# Auto2018.net
KiCad netlist of a schematic drawn in EAGLE
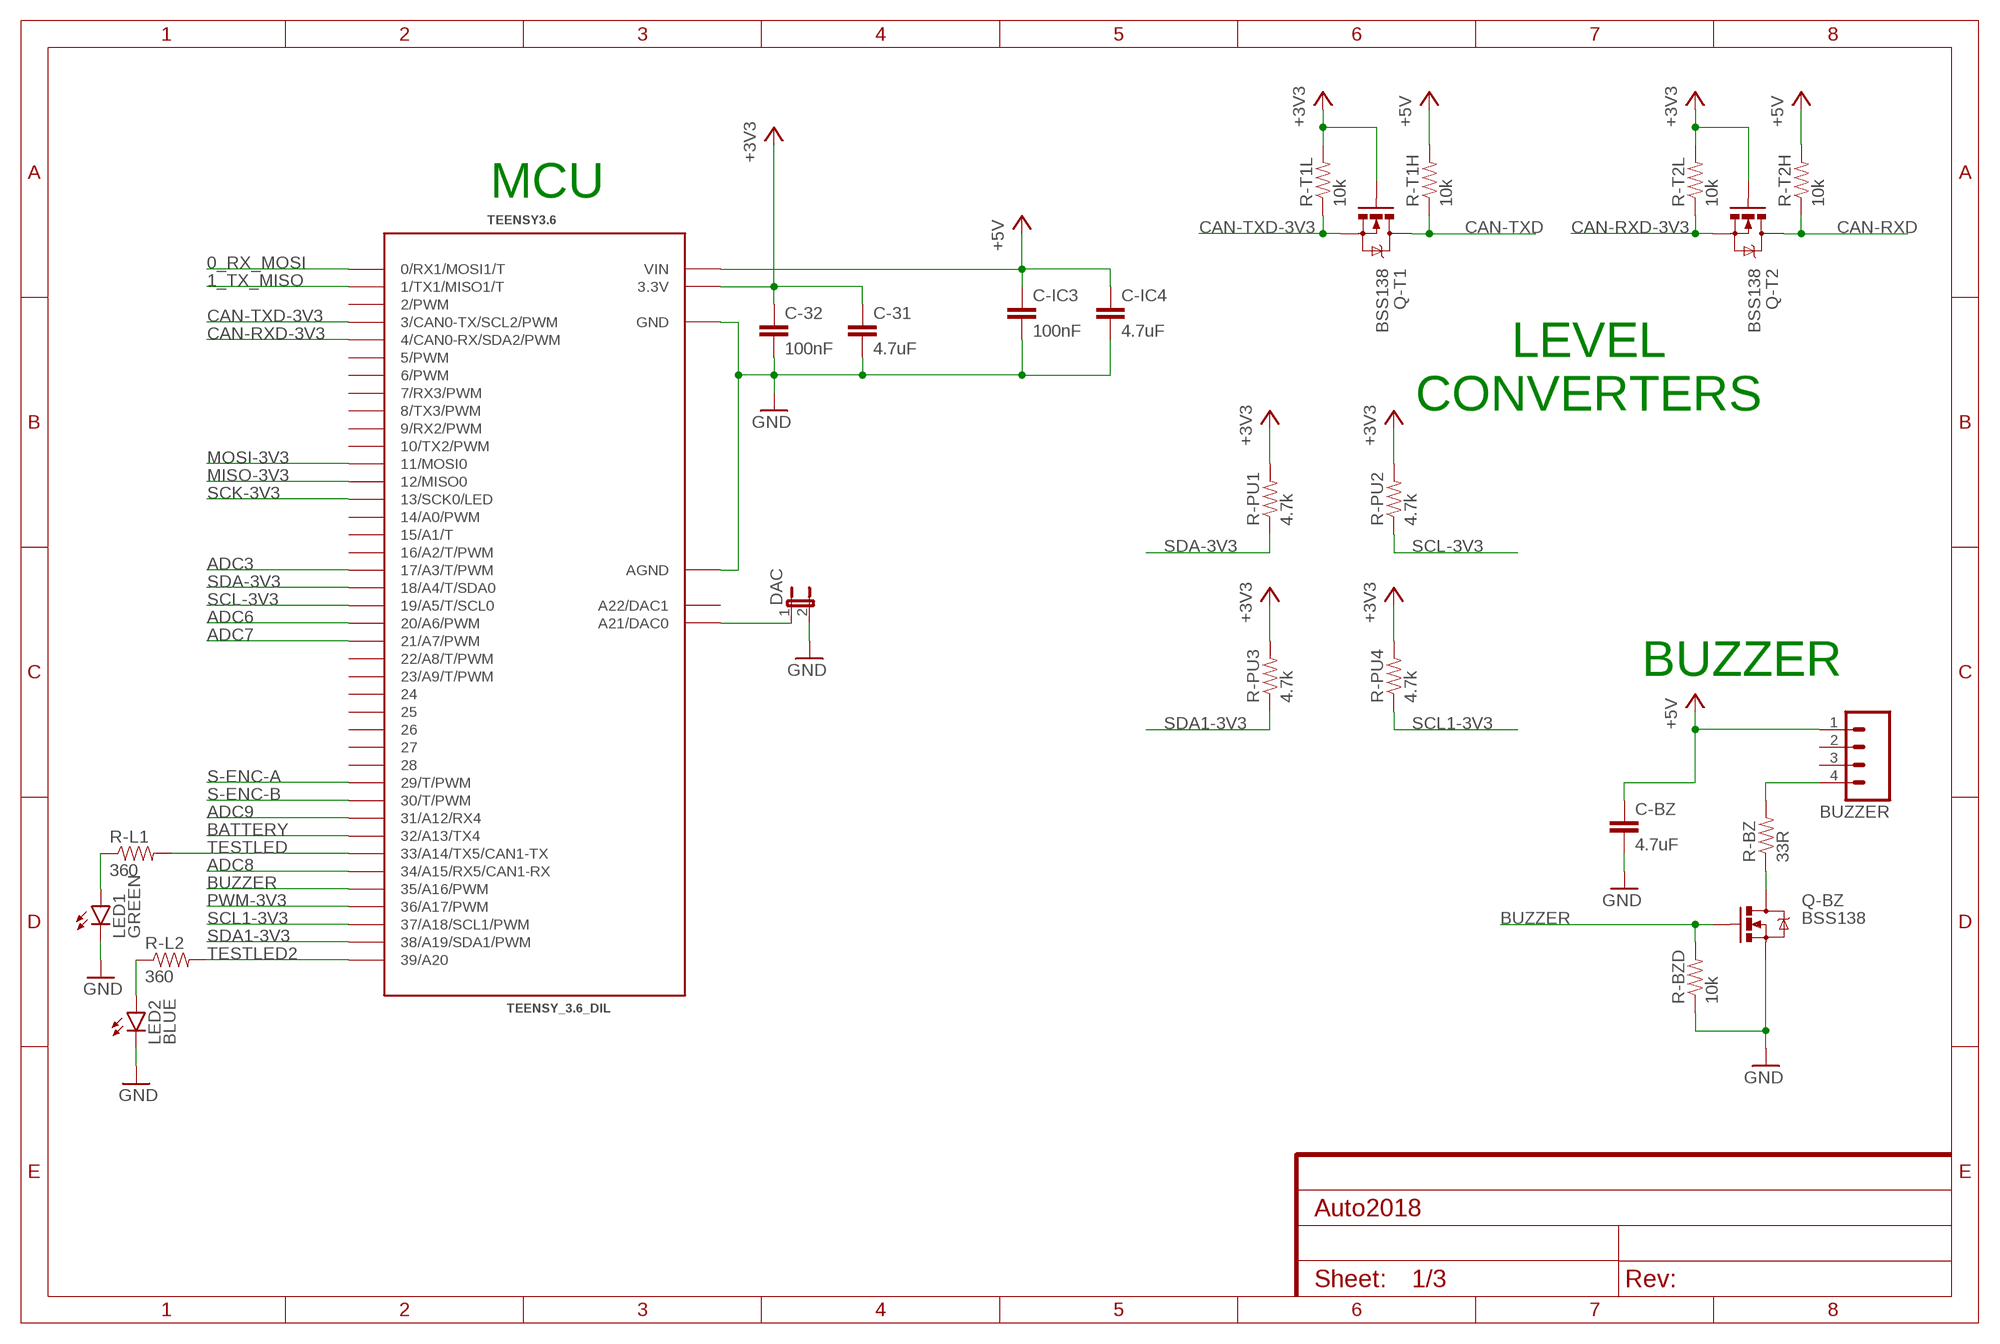
[diagram p0: schematic, sheet 1]
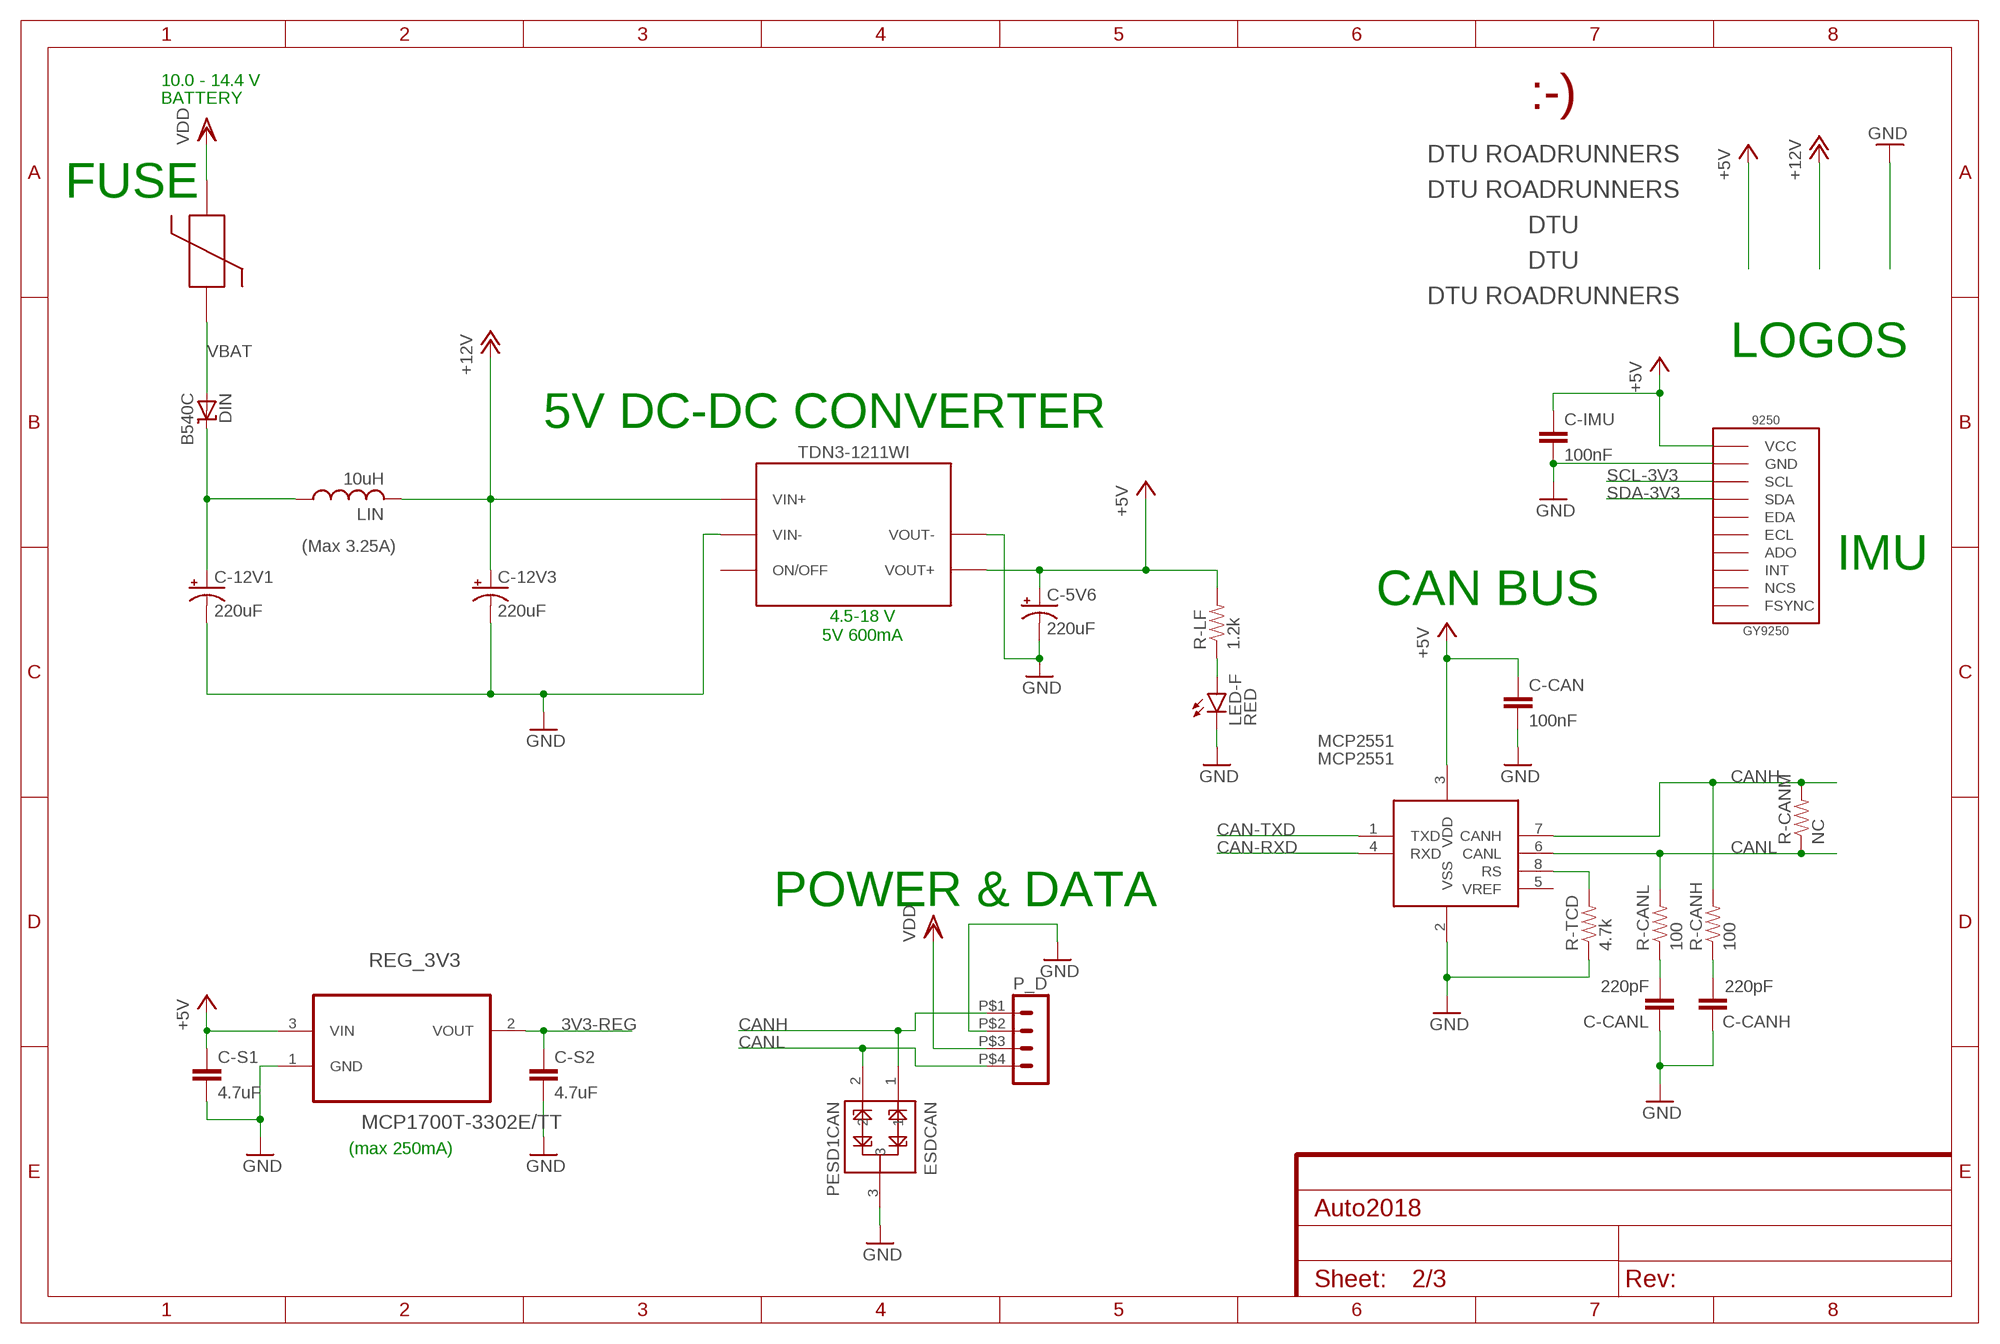
[diagram p1: schematic, sheet 2]
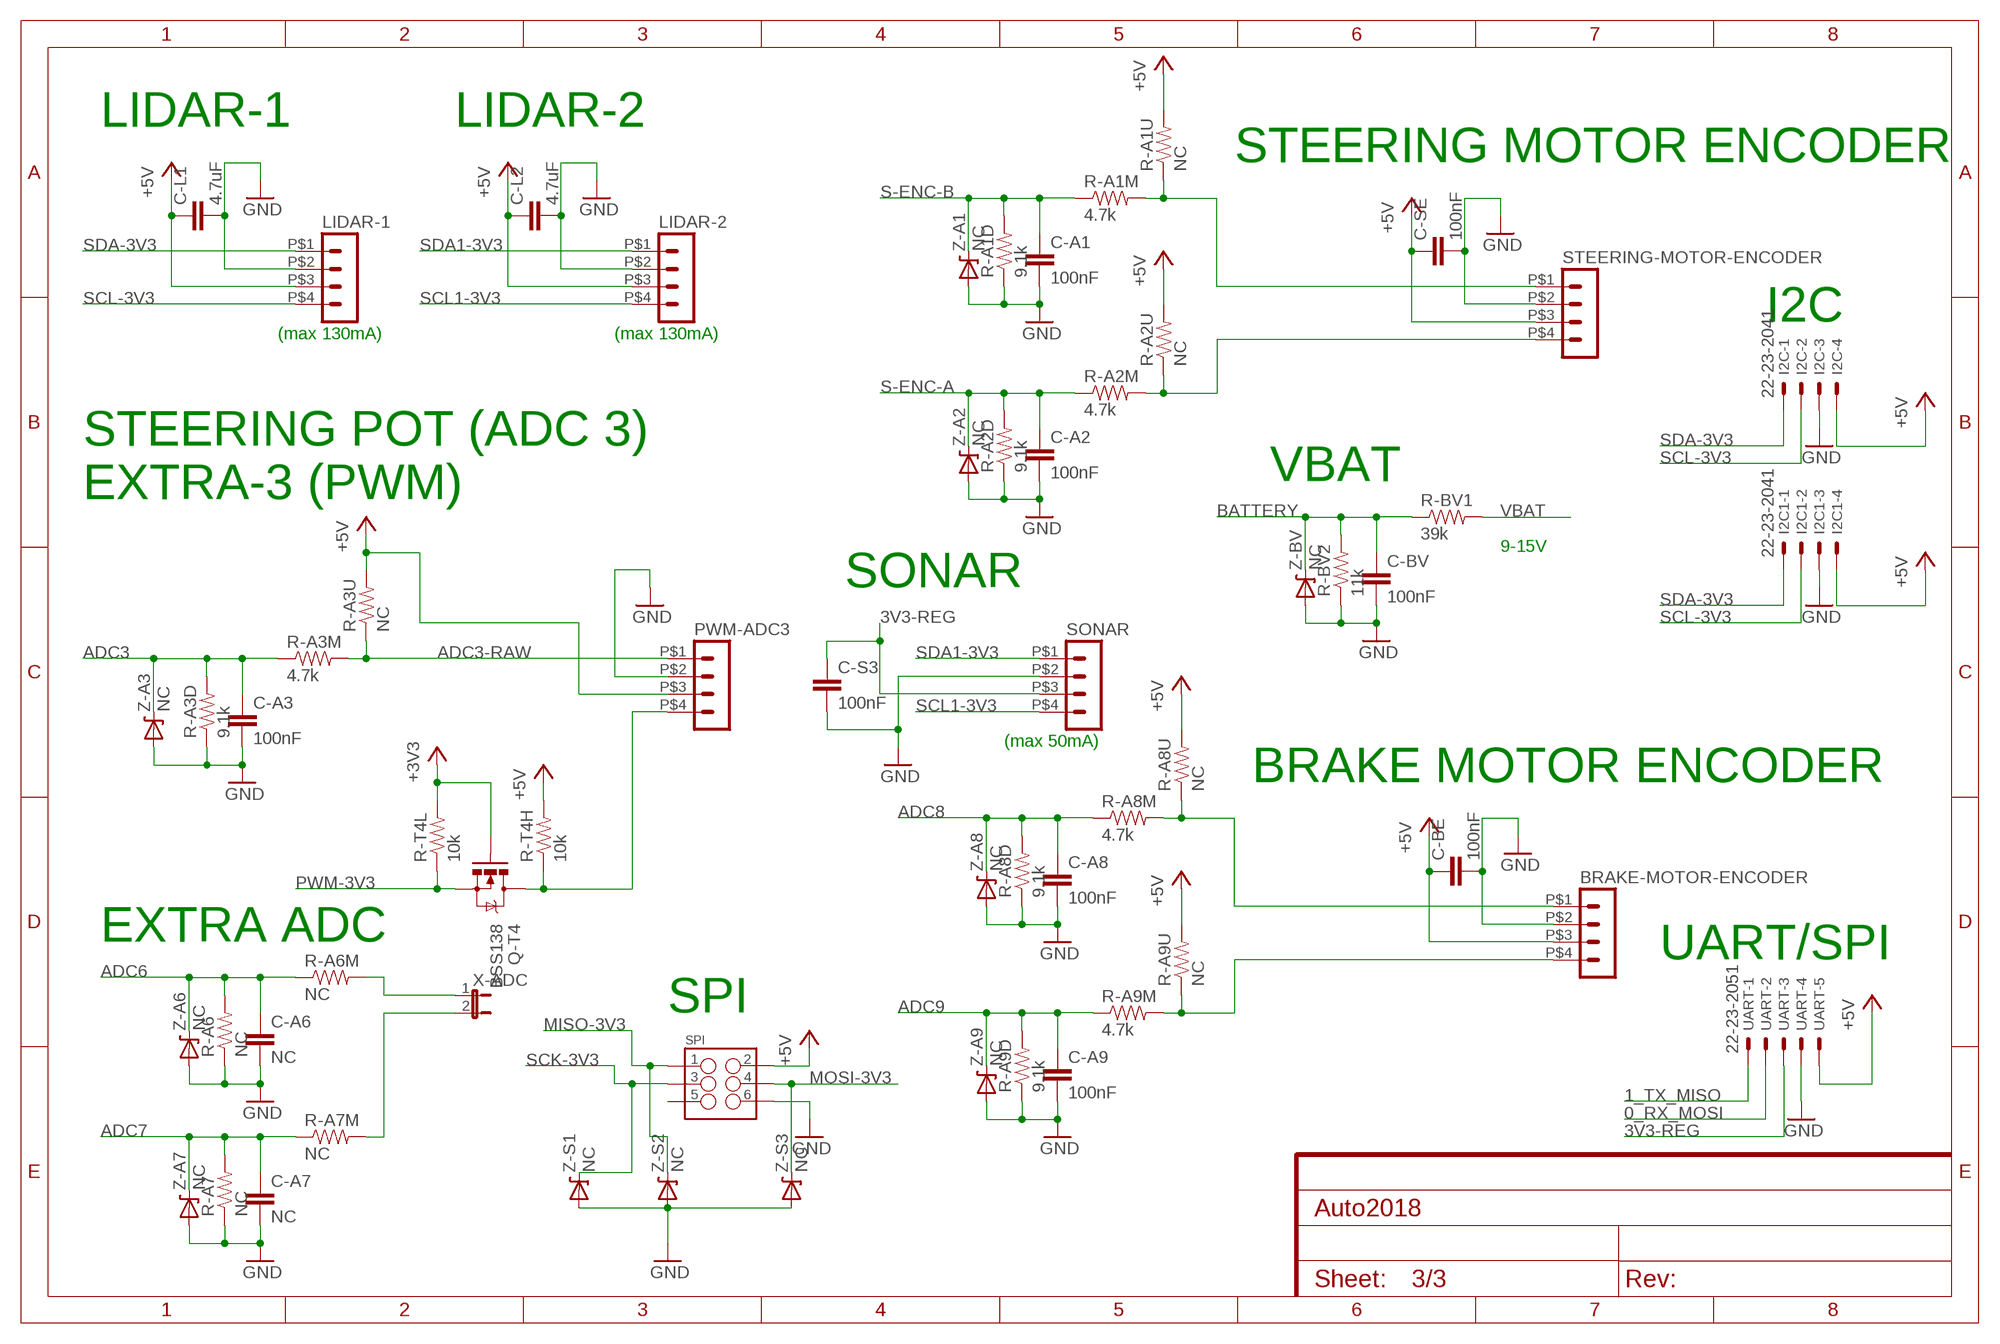
[diagram p2: schematic, sheet 3]

(export (version "E")
  (design (tool "Eeschema 10.0.6"))
  (components
    (comp (ref "BUZZER")
      (value "M04POLAR")
      (footprint "eagle-import:MOLEX-1X4")
      (libsource (lib "eagle-import") (part "M04POLAR"))
    )
    (comp (ref "C-31")
      (value "4.7uF")
      (footprint "eagle-import:1210")
      (libsource (lib "eagle-import") (part "CAP1210"))
    )
    (comp (ref "C-32")
      (value "100nF")
      (footprint "eagle-import:0805")
      (libsource (lib "eagle-import") (part "CAP0805"))
    )
    (comp (ref "C-BZ")
      (value "4.7uF")
      (footprint "eagle-import:1210")
      (libsource (lib "eagle-import") (part "CAP1210"))
    )
    (comp (ref "C-IC3")
      (value "100nF")
      (footprint "eagle-import:0805")
      (libsource (lib "eagle-import") (part "CAP0805"))
    )
    (comp (ref "C-IC4")
      (value "4.7uF")
      (footprint "eagle-import:1210")
      (libsource (lib "eagle-import") (part "CAP1210"))
    )
    (comp (ref "DAC")
      (value "JUMPER-2PTH")
      (footprint "eagle-import:1X02")
      (libsource (lib "eagle-import") (part "JUMPER-2PTH"))
    )
    (comp (ref "LED1")
      (value "GREEN")
      (footprint "eagle-import:LED-1206")
      (libsource (lib "eagle-import") (part "LED1206"))
    )
    (comp (ref "LED2")
      (value "BLUE")
      (footprint "eagle-import:LED-1206")
      (libsource (lib "eagle-import") (part "LED1206"))
    )
    (comp (ref "Q-BZ")
      (value "BSS138")
      (footprint "eagle-import:SOT23-3")
      (libsource (lib "eagle-import") (part "MOSFET-NCHANNELBSS123LT1G"))
    )
    (comp (ref "Q-T1")
      (value "BSS138")
      (footprint "eagle-import:SOT23-3")
      (libsource (lib "eagle-import") (part "MOSFET-NCHANNELBSS123LT1G"))
    )
    (comp (ref "Q-T2")
      (value "BSS138")
      (footprint "eagle-import:SOT23-3")
      (libsource (lib "eagle-import") (part "MOSFET-NCHANNELBSS123LT1G"))
    )
    (comp (ref "R-BZ")
      (value "33R")
      (footprint "eagle-import:0805")
      (libsource (lib "eagle-import") (part "RESISTOR0805-RES"))
    )
    (comp (ref "R-BZD")
      (value "10k")
      (footprint "eagle-import:0805")
      (libsource (lib "eagle-import") (part "RESISTOR0805-RES"))
    )
    (comp (ref "R-L1")
      (value "360")
      (footprint "eagle-import:0805")
      (libsource (lib "eagle-import") (part "RESISTOR0805-RES"))
    )
    (comp (ref "R-L2")
      (value "360")
      (footprint "eagle-import:0805")
      (libsource (lib "eagle-import") (part "RESISTOR0805-RES"))
    )
    (comp (ref "R-PU1")
      (value "4.7k")
      (footprint "eagle-import:0805")
      (libsource (lib "eagle-import") (part "RESISTOR0805-RES"))
    )
    (comp (ref "R-PU2")
      (value "4.7k")
      (footprint "eagle-import:0805")
      (libsource (lib "eagle-import") (part "RESISTOR0805-RES"))
    )
    (comp (ref "R-PU3")
      (value "4.7k")
      (footprint "eagle-import:0805")
      (libsource (lib "eagle-import") (part "RESISTOR0805-RES"))
    )
    (comp (ref "R-PU4")
      (value "4.7k")
      (footprint "eagle-import:0805")
      (libsource (lib "eagle-import") (part "RESISTOR0805-RES"))
    )
    (comp (ref "R-T1H")
      (value "10k")
      (footprint "eagle-import:0805")
      (libsource (lib "eagle-import") (part "RESISTOR0805-RES"))
    )
    (comp (ref "R-T1L")
      (value "10k")
      (footprint "eagle-import:0805")
      (libsource (lib "eagle-import") (part "RESISTOR0805-RES"))
    )
    (comp (ref "R-T2H")
      (value "10k")
      (footprint "eagle-import:0805")
      (libsource (lib "eagle-import") (part "RESISTOR0805-RES"))
    )
    (comp (ref "R-T2L")
      (value "10k")
      (footprint "eagle-import:0805")
      (libsource (lib "eagle-import") (part "RESISTOR0805-RES"))
    )
    (comp (ref "TEENSY3.6")
      (value "TEENSY_3.6_DIL")
      (footprint "eagle-import:TEENSY_3.6_DIL")
      (libsource (lib "eagle-import") (part "TEENSY_3.6_DIL"))
    )
    (comp (ref "9250")
      (value "GY9250")
      (footprint "eagle-import:GY9250")
      (libsource (lib "eagle-import") (part "GY9250"))
    )
    (comp (ref "C-5V6")
      (value "220uF")
      (footprint "eagle-import:PANASONIC_D")
      (libsource (lib "eagle-import") (part "CPOL-USD"))
    )
    (comp (ref "C-12V1")
      (value "220uF")
      (footprint "eagle-import:PANASONIC_D")
      (libsource (lib "eagle-import") (part "CPOL-USD"))
    )
    (comp (ref "C-12V3")
      (value "220uF")
      (footprint "eagle-import:PANASONIC_D")
      (libsource (lib "eagle-import") (part "CPOL-USD"))
    )
    (comp (ref "C-CAN")
      (value "100nF")
      (footprint "eagle-import:0805")
      (libsource (lib "eagle-import") (part "CAP0805"))
    )
    (comp (ref "C-CANH")
      (value "220pF")
      (footprint "eagle-import:0805")
      (libsource (lib "eagle-import") (part "CAP0805"))
    )
    (comp (ref "C-CANL")
      (value "220pF")
      (footprint "eagle-import:0805")
      (libsource (lib "eagle-import") (part "CAP0805"))
    )
    (comp (ref "C-IMU")
      (value "100nF")
      (footprint "eagle-import:0805")
      (libsource (lib "eagle-import") (part "CAP0805"))
    )
    (comp (ref "C-S1")
      (value "4.7uF")
      (footprint "eagle-import:1210")
      (libsource (lib "eagle-import") (part "CAP1210"))
    )
    (comp (ref "C-S2")
      (value "4.7uF")
      (footprint "eagle-import:1210")
      (libsource (lib "eagle-import") (part "CAP1210"))
    )
    (comp (ref "DIN")
      (value "B540C")
      (footprint "eagle-import:SMC")
      (libsource (lib "eagle-import") (part "SD-SMC"))
    )
    (comp (ref "ESDCAN")
      (value "PESD1CAN")
      (footprint "eagle-import:SOT23-3")
      (libsource (lib "eagle-import") (part "PESD1CAN"))
    )
    (comp (ref "LED-F")
      (value "RED")
      (footprint "eagle-import:LED-1206")
      (libsource (lib "eagle-import") (part "LED1206"))
    )
    (comp (ref "LIN")
      (value "10uH")
      (footprint "eagle-import:WE-LHMI_SMD_POWER_INDUCTOR")
      (libsource (lib "eagle-import") (part "WE-LHMI_SMD_POWER_INDUCTOR"))
    )
    (comp (ref "MAIN_FUSE")
      (value "SMF_OMNI-BLOK_FUSE_BLOCK")
      (footprint "eagle-import:SMF_OMNI-BLOK_FUSE_BLOCK")
      (libsource (lib "eagle-import") (part "SMF_OMNI-BLOK_FUSE_BLOCK"))
    )
    (comp (ref "MCP2551")
      (value "MCP2551")
      (footprint "eagle-import:SO-08M")
      (libsource (lib "eagle-import") (part "MCP2551"))
    )
    (comp (ref "P_D")
      (value "HEADER_POS4_43045-0401")
      (footprint "eagle-import:43045-0400")
      (libsource (lib "eagle-import") (part "HEADER_POS4_?43045-0401"))
    )
    (comp (ref "R-CANH")
      (value "100")
      (footprint "eagle-import:0805")
      (libsource (lib "eagle-import") (part "RESISTOR0805-RES"))
    )
    (comp (ref "R-CANL")
      (value "100")
      (footprint "eagle-import:0805")
      (libsource (lib "eagle-import") (part "RESISTOR0805-RES"))
    )
    (comp (ref "R-CANM")
      (value "NC")
      (footprint "eagle-import:0805")
      (libsource (lib "eagle-import") (part "RESISTOR0805-RES"))
    )
    (comp (ref "R-LF")
      (value "1.2k")
      (footprint "eagle-import:0805")
      (libsource (lib "eagle-import") (part "RESISTOR0805-RES"))
    )
    (comp (ref "R-TCD")
      (value "4.7k")
      (footprint "eagle-import:0805")
      (libsource (lib "eagle-import") (part "RESISTOR0805-RES"))
    )
    (comp (ref "REG_3V3")
      (value "MCP1700T-3302E/TT")
      (footprint "eagle-import:SOT95P237X112-3N")
      (libsource (lib "eagle-import") (part "MCP1700T-3302E/TT"))
    )
    (comp (ref "TDN3-1211WI")
      (value "TDN3WI")
      (footprint "eagle-import:TDC3WI")
      (libsource (lib "eagle-import") (part "TDN3WI"))
    )
    (comp (ref "U$3")
      (value "DTUMEDIUM-9MM")
      (footprint "eagle-import:DTU-MEDIUM-9MM")
      (libsource (lib "eagle-import") (part "DTUMEDIUM-9MM"))
    )
    (comp (ref "U$4")
      (value "ROADRUNNERSFULL")
      (footprint "eagle-import:ROADRUNNERS-FULL")
      (libsource (lib "eagle-import") (part "ROADRUNNERSFULL"))
    )
    (comp (ref "U$5")
      (value "ROADRUNNERSSMALL")
      (footprint "eagle-import:ROADRUNNERS-SMALL")
      (libsource (lib "eagle-import") (part "ROADRUNNERSSMALL"))
    )
    (comp (ref "U$6")
      (value "SMILEY")
      (footprint "eagle-import:SMILEY")
      (libsource (lib "eagle-import") (part "SMILEY"))
    )
    (comp (ref "U$8")
      (value "DTUSMALL")
      (footprint "eagle-import:DTU-SMALL-5MM")
      (libsource (lib "eagle-import") (part "DTUSMALL"))
    )
    (comp (ref "U$9")
      (value "ROADRUNNERSFULL")
      (footprint "eagle-import:ROADRUNNERS-FULL")
      (libsource (lib "eagle-import") (part "ROADRUNNERSFULL"))
    )
    (comp (ref "BRAKE-MOTOR-ENCODER")
      (value "HEADER_POS4_43045-0401")
      (footprint "eagle-import:43045-0400")
      (libsource (lib "eagle-import") (part "HEADER_POS4_?43045-0401"))
    )
    (comp (ref "C-A1")
      (value "100nF")
      (footprint "eagle-import:0805")
      (libsource (lib "eagle-import") (part "CAP0805"))
    )
    (comp (ref "C-A2")
      (value "100nF")
      (footprint "eagle-import:0805")
      (libsource (lib "eagle-import") (part "CAP0805"))
    )
    (comp (ref "C-A3")
      (value "100nF")
      (footprint "eagle-import:0805")
      (libsource (lib "eagle-import") (part "CAP0805"))
    )
    (comp (ref "C-A6")
      (value "NC")
      (footprint "eagle-import:0805")
      (libsource (lib "eagle-import") (part "CAP0805"))
    )
    (comp (ref "C-A7")
      (value "NC")
      (footprint "eagle-import:0805")
      (libsource (lib "eagle-import") (part "CAP0805"))
    )
    (comp (ref "C-A8")
      (value "100nF")
      (footprint "eagle-import:0805")
      (libsource (lib "eagle-import") (part "CAP0805"))
    )
    (comp (ref "C-A9")
      (value "100nF")
      (footprint "eagle-import:0805")
      (libsource (lib "eagle-import") (part "CAP0805"))
    )
    (comp (ref "C-BE")
      (value "100nF")
      (footprint "eagle-import:0805")
      (libsource (lib "eagle-import") (part "CAP0805"))
    )
    (comp (ref "C-BV")
      (value "100nF")
      (footprint "eagle-import:0805")
      (libsource (lib "eagle-import") (part "CAP0805"))
    )
    (comp (ref "C-L1")
      (value "4.7uF")
      (footprint "eagle-import:1210")
      (libsource (lib "eagle-import") (part "CAP1210"))
    )
    (comp (ref "C-L2")
      (value "4.7uF")
      (footprint "eagle-import:1210")
      (libsource (lib "eagle-import") (part "CAP1210"))
    )
    (comp (ref "C-S3")
      (value "100nF")
      (footprint "eagle-import:0805")
      (libsource (lib "eagle-import") (part "CAP0805"))
    )
    (comp (ref "C-SE")
      (value "100nF")
      (footprint "eagle-import:0805")
      (libsource (lib "eagle-import") (part "CAP0805"))
    )
    (comp (ref "I2C")
      (value "22-23-2041")
      (footprint "eagle-import:22-23-2041")
      (fields (field (name "MF") "MOLEX"))
      (libsource (lib "eagle-import") (part "22-23-2041"))
    )
    (comp (ref "I2C1")
      (value "22-23-2041")
      (footprint "eagle-import:22-23-2041")
      (fields (field (name "MF") "MOLEX"))
      (libsource (lib "eagle-import") (part "22-23-2041"))
    )
    (comp (ref "LIDAR-1")
      (value "HEADER_POS4_43045-0401")
      (footprint "eagle-import:43045-0400")
      (libsource (lib "eagle-import") (part "HEADER_POS4_?43045-0401"))
    )
    (comp (ref "LIDAR-2")
      (value "HEADER_POS4_43045-0401")
      (footprint "eagle-import:43045-0400")
      (libsource (lib "eagle-import") (part "HEADER_POS4_?43045-0401"))
    )
    (comp (ref "PWM-ADC3")
      (value "HEADER_POS4_43045-0401")
      (footprint "eagle-import:43045-0400")
      (libsource (lib "eagle-import") (part "HEADER_POS4_?43045-0401"))
    )
    (comp (ref "Q-T4")
      (value "BSS138")
      (footprint "eagle-import:SOT23-3")
      (libsource (lib "eagle-import") (part "MOSFET-NCHANNELBSS123LT1G"))
    )
    (comp (ref "R-A1D")
      (value "9.1k")
      (footprint "eagle-import:0805")
      (libsource (lib "eagle-import") (part "RESISTOR0805-RES"))
    )
    (comp (ref "R-A1M")
      (value "4.7k")
      (footprint "eagle-import:0805")
      (libsource (lib "eagle-import") (part "RESISTOR0805-RES"))
    )
    (comp (ref "R-A1U")
      (value "NC")
      (footprint "eagle-import:0805")
      (libsource (lib "eagle-import") (part "RESISTOR0805-RES"))
    )
    (comp (ref "R-A2D")
      (value "9.1k")
      (footprint "eagle-import:0805")
      (libsource (lib "eagle-import") (part "RESISTOR0805-RES"))
    )
    (comp (ref "R-A2M")
      (value "4.7k")
      (footprint "eagle-import:0805")
      (libsource (lib "eagle-import") (part "RESISTOR0805-RES"))
    )
    (comp (ref "R-A2U")
      (value "NC")
      (footprint "eagle-import:0805")
      (libsource (lib "eagle-import") (part "RESISTOR0805-RES"))
    )
    (comp (ref "R-A3D")
      (value "9.1k")
      (footprint "eagle-import:0805")
      (libsource (lib "eagle-import") (part "RESISTOR0805-RES"))
    )
    (comp (ref "R-A3M")
      (value "4.7k")
      (footprint "eagle-import:0805")
      (libsource (lib "eagle-import") (part "RESISTOR0805-RES"))
    )
    (comp (ref "R-A3U")
      (value "NC")
      (footprint "eagle-import:0805")
      (libsource (lib "eagle-import") (part "RESISTOR0805-RES"))
    )
    (comp (ref "R-A6")
      (value "NC")
      (footprint "eagle-import:0805")
      (libsource (lib "eagle-import") (part "RESISTOR0805-RES"))
    )
    (comp (ref "R-A6M")
      (value "NC")
      (footprint "eagle-import:0805")
      (libsource (lib "eagle-import") (part "RESISTOR0805-RES"))
    )
    (comp (ref "R-A7")
      (value "NC")
      (footprint "eagle-import:0805")
      (libsource (lib "eagle-import") (part "RESISTOR0805-RES"))
    )
    (comp (ref "R-A7M")
      (value "NC")
      (footprint "eagle-import:0805")
      (libsource (lib "eagle-import") (part "RESISTOR0805-RES"))
    )
    (comp (ref "R-A8D")
      (value "9.1k")
      (footprint "eagle-import:0805")
      (libsource (lib "eagle-import") (part "RESISTOR0805-RES"))
    )
    (comp (ref "R-A8M")
      (value "4.7k")
      (footprint "eagle-import:0805")
      (libsource (lib "eagle-import") (part "RESISTOR0805-RES"))
    )
    (comp (ref "R-A8U")
      (value "NC")
      (footprint "eagle-import:0805")
      (libsource (lib "eagle-import") (part "RESISTOR0805-RES"))
    )
    (comp (ref "R-A9D")
      (value "9.1k")
      (footprint "eagle-import:0805")
      (libsource (lib "eagle-import") (part "RESISTOR0805-RES"))
    )
    (comp (ref "R-A9M")
      (value "4.7k")
      (footprint "eagle-import:0805")
      (libsource (lib "eagle-import") (part "RESISTOR0805-RES"))
    )
    (comp (ref "R-A9U")
      (value "NC")
      (footprint "eagle-import:0805")
      (libsource (lib "eagle-import") (part "RESISTOR0805-RES"))
    )
    (comp (ref "R-BV1")
      (value "39k")
      (footprint "eagle-import:0805")
      (libsource (lib "eagle-import") (part "RESISTOR0805-RES"))
    )
    (comp (ref "R-BV2")
      (value "11k")
      (footprint "eagle-import:0805")
      (libsource (lib "eagle-import") (part "RESISTOR0805-RES"))
    )
    (comp (ref "R-T4H")
      (value "10k")
      (footprint "eagle-import:0805")
      (libsource (lib "eagle-import") (part "RESISTOR0805-RES"))
    )
    (comp (ref "R-T4L")
      (value "10k")
      (footprint "eagle-import:0805")
      (libsource (lib "eagle-import") (part "RESISTOR0805-RES"))
    )
    (comp (ref "SONAR")
      (value "HEADER_POS4_43045-0401")
      (footprint "eagle-import:43045-0400")
      (libsource (lib "eagle-import") (part "HEADER_POS4_?43045-0401"))
    )
    (comp (ref "SPI")
      (value "M03X2POGO_PINS")
      (footprint "eagle-import:2X3_POGO")
      (libsource (lib "eagle-import") (part "M03X2POGO_PINS"))
    )
    (comp (ref "STEERING-MOTOR-ENCODER")
      (value "HEADER_POS4_43045-0401")
      (footprint "eagle-import:43045-0400")
      (libsource (lib "eagle-import") (part "HEADER_POS4_?43045-0401"))
    )
    (comp (ref "UART")
      (value "22-23-2051")
      (footprint "eagle-import:22-23-2051")
      (fields (field (name "MF") "MOLEX"))
      (libsource (lib "eagle-import") (part "22-23-2051"))
    )
    (comp (ref "X-ADC")
      (value "JUMPER-2PTH")
      (footprint "eagle-import:1X02")
      (libsource (lib "eagle-import") (part "JUMPER-2PTH"))
    )
    (comp (ref "Z-A1")
      (value "NC")
      (footprint "eagle-import:SOD123@1")
      (libsource (lib "eagle-import") (part "ZENER"))
    )
    (comp (ref "Z-A2")
      (value "NC")
      (footprint "eagle-import:SOD123@1")
      (libsource (lib "eagle-import") (part "ZENER"))
    )
    (comp (ref "Z-A3")
      (value "NC")
      (footprint "eagle-import:SOD123@1")
      (libsource (lib "eagle-import") (part "ZENER"))
    )
    (comp (ref "Z-A6")
      (value "NC")
      (footprint "eagle-import:SOD123@1")
      (libsource (lib "eagle-import") (part "ZENER"))
    )
    (comp (ref "Z-A7")
      (value "NC")
      (footprint "eagle-import:SOD123@1")
      (libsource (lib "eagle-import") (part "ZENER"))
    )
    (comp (ref "Z-A8")
      (value "NC")
      (footprint "eagle-import:SOD123@1")
      (libsource (lib "eagle-import") (part "ZENER"))
    )
    (comp (ref "Z-A9")
      (value "NC")
      (footprint "eagle-import:SOD123@1")
      (libsource (lib "eagle-import") (part "ZENER"))
    )
    (comp (ref "Z-BV")
      (value "NC")
      (footprint "eagle-import:SOD123@1")
      (libsource (lib "eagle-import") (part "ZENER"))
    )
    (comp (ref "Z-S1")
      (value "NC")
      (footprint "eagle-import:SOD123@1")
      (libsource (lib "eagle-import") (part "ZENER"))
    )
    (comp (ref "Z-S2")
      (value "NC")
      (footprint "eagle-import:SOD123@1")
      (libsource (lib "eagle-import") (part "ZENER"))
    )
    (comp (ref "Z-S3")
      (value "NC")
      (footprint "eagle-import:SOD123@1")
      (libsource (lib "eagle-import") (part "ZENER"))
    )
  )
  (nets
    (net (code "1") (name "+3V3") (class "Default")
      (node (ref "C-31") (pin "1") (pinfunction "1_1") (pintype "passive"))
      (node (ref "C-32") (pin "1") (pinfunction "1_1") (pintype "passive"))
      (node (ref "Q-T1") (pin "1") (pinfunction "G_1") (pintype "passive"))
      (node (ref "Q-T2") (pin "1") (pinfunction "G_1") (pintype "passive"))
      (node (ref "Q-T4") (pin "1") (pinfunction "G_1") (pintype "passive"))
      (node (ref "R-PU1") (pin "2") (pinfunction "2_2") (pintype "passive"))
      (node (ref "R-PU2") (pin "2") (pinfunction "2_2") (pintype "passive"))
      (node (ref "R-PU3") (pin "2") (pinfunction "2_2") (pintype "passive"))
      (node (ref "R-PU4") (pin "2") (pinfunction "2_2") (pintype "passive"))
      (node (ref "R-T1L") (pin "2") (pinfunction "2_2") (pintype "passive"))
      (node (ref "R-T2L") (pin "2") (pinfunction "2_2") (pintype "passive"))
      (node (ref "R-T4L") (pin "2") (pinfunction "2_2") (pintype "passive"))
      (node (ref "TEENSY3.6") (pin "3.3V") (pinfunction "3.3V_3.3V") (pintype "power_in"))
      (node (ref "TEENSY3.6") (pin "3.3V3") (pinfunction "3.3V_3.3V3") (pintype "power_in"))
    )
    (net (code "2") (name "+5V") (class "Default")
      (node (ref "9250") (pin "P$VCC") (pinfunction "VCC_P$VCC") (pintype "bidirectional"))
      (node (ref "BRAKE-MOTOR-ENCODER") (pin "P$3") (pinfunction "3_P$3") (pintype "passive"))
      (node (ref "BUZZER") (pin "1") (pinfunction "1_1") (pintype "passive"))
      (node (ref "C-5V6") (pin "+") (pinfunction "+_+") (pintype "passive"))
      (node (ref "C-BE") (pin "1") (pinfunction "1_1") (pintype "passive"))
      (node (ref "C-BZ") (pin "1") (pinfunction "1_1") (pintype "passive"))
      (node (ref "C-CAN") (pin "1") (pinfunction "1_1") (pintype "passive"))
      (node (ref "C-IC3") (pin "1") (pinfunction "1_1") (pintype "passive"))
      (node (ref "C-IC4") (pin "1") (pinfunction "1_1") (pintype "passive"))
      (node (ref "C-IMU") (pin "1") (pinfunction "1_1") (pintype "passive"))
      (node (ref "C-L1") (pin "1") (pinfunction "1_1") (pintype "passive"))
      (node (ref "C-L2") (pin "1") (pinfunction "1_1") (pintype "passive"))
      (node (ref "C-S1") (pin "1") (pinfunction "1_1") (pintype "passive"))
      (node (ref "C-SE") (pin "1") (pinfunction "1_1") (pintype "passive"))
      (node (ref "I2C") (pin "4") (pinfunction "S_4") (pintype "passive"))
      (node (ref "I2C1") (pin "4") (pinfunction "S_4") (pintype "passive"))
      (node (ref "LIDAR-1") (pin "P$3") (pinfunction "3_P$3") (pintype "passive"))
      (node (ref "LIDAR-2") (pin "P$3") (pinfunction "3_P$3") (pintype "passive"))
      (node (ref "MCP2551") (pin "3") (pinfunction "VDD_3") (pintype "power_in"))
      (node (ref "PWM-ADC3") (pin "P$3") (pinfunction "3_P$3") (pintype "passive"))
      (node (ref "R-A1U") (pin "2") (pinfunction "2_2") (pintype "passive"))
      (node (ref "R-A2U") (pin "2") (pinfunction "2_2") (pintype "passive"))
      (node (ref "R-A3U") (pin "2") (pinfunction "2_2") (pintype "passive"))
      (node (ref "R-A8U") (pin "2") (pinfunction "2_2") (pintype "passive"))
      (node (ref "R-A9U") (pin "2") (pinfunction "2_2") (pintype "passive"))
      (node (ref "R-LF") (pin "2") (pinfunction "2_2") (pintype "passive"))
      (node (ref "R-T1H") (pin "2") (pinfunction "2_2") (pintype "passive"))
      (node (ref "R-T2H") (pin "2") (pinfunction "2_2") (pintype "passive"))
      (node (ref "R-T4H") (pin "2") (pinfunction "2_2") (pintype "passive"))
      (node (ref "REG_3V3") (pin "3") (pinfunction "VIN_3") (pintype "input"))
      (node (ref "SPI") (pin "P$2") (pinfunction "2_P$2") (pintype "bidirectional"))
      (node (ref "STEERING-MOTOR-ENCODER") (pin "P$3") (pinfunction "3_P$3") (pintype "passive"))
      (node (ref "TDN3-1211WI") (pin "VOUT+") (pinfunction "VOUT+_VOUT+") (pintype "bidirectional"))
      (node (ref "TEENSY3.6") (pin "VIN") (pinfunction "VIN_VIN") (pintype "power_in"))
      (node (ref "UART") (pin "5") (pinfunction "S_5") (pintype "passive"))
    )
    (net (code "3") (name "+12V") (class "Default")
      (node (ref "C-12V3") (pin "+") (pinfunction "+_+") (pintype "passive"))
      (node (ref "LIN") (pin "P$2") (pinfunction "2_P$2") (pintype "passive"))
      (node (ref "TDN3-1211WI") (pin "VIN+") (pinfunction "VIN+_VIN+") (pintype "bidirectional"))
    )
    (net (code "4") (name "0_RX_MOSI") (class "Default")
      (node (ref "TEENSY3.6") (pin "0") (pinfunction "0/RX1/MOSI1/T_0") (pintype "bidirectional"))
      (node (ref "UART") (pin "2") (pinfunction "S_2") (pintype "passive"))
    )
    (net (code "5") (name "1_TX_MISO") (class "Default")
      (node (ref "TEENSY3.6") (pin "1") (pinfunction "1/TX1/MISO1/T_1") (pintype "bidirectional"))
      (node (ref "UART") (pin "1") (pinfunction "S_1") (pintype "passive"))
    )
    (net (code "6") (name "3V3-REG") (class "Default")
      (node (ref "C-S2") (pin "1") (pinfunction "1_1") (pintype "passive"))
      (node (ref "C-S3") (pin "1") (pinfunction "1_1") (pintype "passive"))
      (node (ref "REG_3V3") (pin "2") (pinfunction "VOUT_2") (pintype "output"))
      (node (ref "SONAR") (pin "P$3") (pinfunction "3_P$3") (pintype "passive"))
      (node (ref "UART") (pin "3") (pinfunction "S_3") (pintype "passive"))
    )
    (net (code "7") (name "ADC3") (class "Default")
      (node (ref "C-A3") (pin "1") (pinfunction "1_1") (pintype "passive"))
      (node (ref "R-A3D") (pin "2") (pinfunction "2_2") (pintype "passive"))
      (node (ref "R-A3M") (pin "1") (pinfunction "1_1") (pintype "passive"))
      (node (ref "TEENSY3.6") (pin "17/A3") (pinfunction "17/A3/T/PWM_17/A3") (pintype "bidirectional"))
      (node (ref "Z-A3") (pin "C") (pinfunction "C_C") (pintype "passive"))
    )
    (net (code "8") (name "ADC3-RAW") (class "Default")
      (node (ref "PWM-ADC3") (pin "P$1") (pinfunction "1_P$1") (pintype "passive"))
      (node (ref "R-A3M") (pin "2") (pinfunction "2_2") (pintype "passive"))
      (node (ref "R-A3U") (pin "1") (pinfunction "1_1") (pintype "passive"))
    )
    (net (code "9") (name "ADC6") (class "Default")
      (node (ref "C-A6") (pin "1") (pinfunction "1_1") (pintype "passive"))
      (node (ref "R-A6") (pin "2") (pinfunction "2_2") (pintype "passive"))
      (node (ref "R-A6M") (pin "1") (pinfunction "1_1") (pintype "passive"))
      (node (ref "TEENSY3.6") (pin "20/A6") (pinfunction "20/A6/PWM_20/A6") (pintype "bidirectional"))
      (node (ref "Z-A6") (pin "C") (pinfunction "C_C") (pintype "passive"))
    )
    (net (code "10") (name "ADC7") (class "Default")
      (node (ref "C-A7") (pin "1") (pinfunction "1_1") (pintype "passive"))
      (node (ref "R-A7") (pin "2") (pinfunction "2_2") (pintype "passive"))
      (node (ref "R-A7M") (pin "1") (pinfunction "1_1") (pintype "passive"))
      (node (ref "TEENSY3.6") (pin "21/A7") (pinfunction "21/A7/PWM_21/A7") (pintype "bidirectional"))
      (node (ref "Z-A7") (pin "C") (pinfunction "C_C") (pintype "passive"))
    )
    (net (code "11") (name "ADC8") (class "Default")
      (node (ref "C-A8") (pin "1") (pinfunction "1_1") (pintype "passive"))
      (node (ref "R-A8D") (pin "2") (pinfunction "2_2") (pintype "passive"))
      (node (ref "R-A8M") (pin "1") (pinfunction "1_1") (pintype "passive"))
      (node (ref "TEENSY3.6") (pin "34/A15") (pinfunction "34/A15/RX5/CAN1-RX_34/A15") (pintype "bidirectional"))
      (node (ref "Z-A8") (pin "C") (pinfunction "C_C") (pintype "passive"))
    )
    (net (code "12") (name "ADC9") (class "Default")
      (node (ref "C-A9") (pin "1") (pinfunction "1_1") (pintype "passive"))
      (node (ref "R-A9D") (pin "2") (pinfunction "2_2") (pintype "passive"))
      (node (ref "R-A9M") (pin "1") (pinfunction "1_1") (pintype "passive"))
      (node (ref "TEENSY3.6") (pin "31/A12") (pinfunction "31/A12/RX4_31/A12") (pintype "bidirectional"))
      (node (ref "Z-A9") (pin "C") (pinfunction "C_C") (pintype "passive"))
    )
    (net (code "13") (name "BATTERY") (class "Default")
      (node (ref "C-BV") (pin "1") (pinfunction "1_1") (pintype "passive"))
      (node (ref "R-BV1") (pin "1") (pinfunction "1_1") (pintype "passive"))
      (node (ref "R-BV2") (pin "2") (pinfunction "2_2") (pintype "passive"))
      (node (ref "TEENSY3.6") (pin "32/A13") (pinfunction "32/A13/TX4_32/A13") (pintype "bidirectional"))
      (node (ref "Z-BV") (pin "C") (pinfunction "C_C") (pintype "passive"))
    )
    (net (code "14") (name "BUZZER") (class "Default")
      (node (ref "Q-BZ") (pin "1") (pinfunction "G_1") (pintype "passive"))
      (node (ref "R-BZD") (pin "2") (pinfunction "2_2") (pintype "passive"))
      (node (ref "TEENSY3.6") (pin "35/A16") (pinfunction "35/A16/PWM_35/A16") (pintype "bidirectional"))
    )
    (net (code "15") (name "CAN-RXD") (class "Default")
      (node (ref "MCP2551") (pin "4") (pinfunction "RXD_4") (pintype "bidirectional"))
      (node (ref "Q-T2") (pin "3") (pinfunction "D_3") (pintype "passive"))
      (node (ref "R-T2H") (pin "1") (pinfunction "1_1") (pintype "passive"))
    )
    (net (code "16") (name "CAN-RXD-3V3") (class "Default")
      (node (ref "Q-T2") (pin "2") (pinfunction "S_2") (pintype "passive"))
      (node (ref "R-T2L") (pin "1") (pinfunction "1_1") (pintype "passive"))
      (node (ref "TEENSY3.6") (pin "4") (pinfunction "4/CAN0-RX/SDA2/PWM_4") (pintype "bidirectional"))
    )
    (net (code "17") (name "CAN-TXD") (class "Default")
      (node (ref "MCP2551") (pin "1") (pinfunction "TXD_1") (pintype "bidirectional"))
      (node (ref "Q-T1") (pin "3") (pinfunction "D_3") (pintype "passive"))
      (node (ref "R-T1H") (pin "1") (pinfunction "1_1") (pintype "passive"))
    )
    (net (code "18") (name "CAN-TXD-3V3") (class "Default")
      (node (ref "Q-T1") (pin "2") (pinfunction "S_2") (pintype "passive"))
      (node (ref "R-T1L") (pin "1") (pinfunction "1_1") (pintype "passive"))
      (node (ref "TEENSY3.6") (pin "3") (pinfunction "3/CAN0-TX/SCL2/PWM_3") (pintype "bidirectional"))
    )
    (net (code "19") (name "CANH") (class "Default")
      (node (ref "ESDCAN") (pin "1") (pinfunction "1_1") (pintype "bidirectional"))
      (node (ref "MCP2551") (pin "7") (pinfunction "CANH_7") (pintype "bidirectional"))
      (node (ref "P_D") (pin "P$1") (pinfunction "1_P$1") (pintype "passive"))
      (node (ref "R-CANH") (pin "2") (pinfunction "2_2") (pintype "passive"))
      (node (ref "R-CANM") (pin "2") (pinfunction "2_2") (pintype "passive"))
    )
    (net (code "20") (name "CANL") (class "Default")
      (node (ref "ESDCAN") (pin "2") (pinfunction "2_2") (pintype "bidirectional"))
      (node (ref "MCP2551") (pin "6") (pinfunction "CANL_6") (pintype "bidirectional"))
      (node (ref "P_D") (pin "P$4") (pinfunction "4_P$4") (pintype "passive"))
      (node (ref "R-CANL") (pin "2") (pinfunction "2_2") (pintype "passive"))
      (node (ref "R-CANM") (pin "1") (pinfunction "1_1") (pintype "passive"))
    )
    (net (code "21") (name "GND") (class "Default")
      (node (ref "9250") (pin "P$GND") (pinfunction "GND_P$GND") (pintype "bidirectional"))
      (node (ref "BRAKE-MOTOR-ENCODER") (pin "P$2") (pinfunction "2_P$2") (pintype "passive"))
      (node (ref "C-12V1") (pin "-") (pinfunction "-_-") (pintype "passive"))
      (node (ref "C-12V3") (pin "-") (pinfunction "-_-") (pintype "passive"))
      (node (ref "C-31") (pin "2") (pinfunction "2_2") (pintype "passive"))
      (node (ref "C-32") (pin "2") (pinfunction "2_2") (pintype "passive"))
      (node (ref "C-5V6") (pin "-") (pinfunction "-_-") (pintype "passive"))
      (node (ref "C-A1") (pin "2") (pinfunction "2_2") (pintype "passive"))
      (node (ref "C-A2") (pin "2") (pinfunction "2_2") (pintype "passive"))
      (node (ref "C-A3") (pin "2") (pinfunction "2_2") (pintype "passive"))
      (node (ref "C-A6") (pin "2") (pinfunction "2_2") (pintype "passive"))
      (node (ref "C-A7") (pin "2") (pinfunction "2_2") (pintype "passive"))
      (node (ref "C-A8") (pin "2") (pinfunction "2_2") (pintype "passive"))
      (node (ref "C-A9") (pin "2") (pinfunction "2_2") (pintype "passive"))
      (node (ref "C-BE") (pin "2") (pinfunction "2_2") (pintype "passive"))
      (node (ref "C-BV") (pin "2") (pinfunction "2_2") (pintype "passive"))
      (node (ref "C-BZ") (pin "2") (pinfunction "2_2") (pintype "passive"))
      (node (ref "C-CAN") (pin "2") (pinfunction "2_2") (pintype "passive"))
      (node (ref "C-CANH") (pin "1") (pinfunction "1_1") (pintype "passive"))
      (node (ref "C-CANL") (pin "1") (pinfunction "1_1") (pintype "passive"))
      (node (ref "C-IC3") (pin "2") (pinfunction "2_2") (pintype "passive"))
      (node (ref "C-IC4") (pin "2") (pinfunction "2_2") (pintype "passive"))
      (node (ref "C-IMU") (pin "2") (pinfunction "2_2") (pintype "passive"))
      (node (ref "C-L1") (pin "2") (pinfunction "2_2") (pintype "passive"))
      (node (ref "C-L2") (pin "2") (pinfunction "2_2") (pintype "passive"))
      (node (ref "C-S1") (pin "2") (pinfunction "2_2") (pintype "passive"))
      (node (ref "C-S2") (pin "2") (pinfunction "2_2") (pintype "passive"))
      (node (ref "C-S3") (pin "2") (pinfunction "2_2") (pintype "passive"))
      (node (ref "C-SE") (pin "2") (pinfunction "2_2") (pintype "passive"))
      (node (ref "DAC") (pin "2") (pinfunction "2_2") (pintype "passive"))
      (node (ref "ESDCAN") (pin "3") (pinfunction "3_3") (pintype "bidirectional"))
      (node (ref "I2C") (pin "3") (pinfunction "S_3") (pintype "passive"))
      (node (ref "I2C1") (pin "3") (pinfunction "S_3") (pintype "passive"))
      (node (ref "LED-F") (pin "C") (pinfunction "C_C") (pintype "passive"))
      (node (ref "LED1") (pin "C") (pinfunction "C_C") (pintype "passive"))
      (node (ref "LED2") (pin "C") (pinfunction "C_C") (pintype "passive"))
      (node (ref "LIDAR-1") (pin "P$2") (pinfunction "2_P$2") (pintype "passive"))
      (node (ref "LIDAR-2") (pin "P$2") (pinfunction "2_P$2") (pintype "passive"))
      (node (ref "MCP2551") (pin "2") (pinfunction "VSS_2") (pintype "power_in"))
      (node (ref "PWM-ADC3") (pin "P$2") (pinfunction "2_P$2") (pintype "passive"))
      (node (ref "P_D") (pin "P$2") (pinfunction "2_P$2") (pintype "passive"))
      (node (ref "Q-BZ") (pin "2") (pinfunction "S_2") (pintype "passive"))
      (node (ref "R-A1D") (pin "1") (pinfunction "1_1") (pintype "passive"))
      (node (ref "R-A2D") (pin "1") (pinfunction "1_1") (pintype "passive"))
      (node (ref "R-A3D") (pin "1") (pinfunction "1_1") (pintype "passive"))
      (node (ref "R-A6") (pin "1") (pinfunction "1_1") (pintype "passive"))
      (node (ref "R-A7") (pin "1") (pinfunction "1_1") (pintype "passive"))
      (node (ref "R-A8D") (pin "1") (pinfunction "1_1") (pintype "passive"))
      (node (ref "R-A9D") (pin "1") (pinfunction "1_1") (pintype "passive"))
      (node (ref "R-BV2") (pin "1") (pinfunction "1_1") (pintype "passive"))
      (node (ref "R-BZD") (pin "1") (pinfunction "1_1") (pintype "passive"))
      (node (ref "R-TCD") (pin "1") (pinfunction "1_1") (pintype "passive"))
      (node (ref "REG_3V3") (pin "1") (pinfunction "GND_1") (pintype "passive"))
      (node (ref "SONAR") (pin "P$2") (pinfunction "2_P$2") (pintype "passive"))
      (node (ref "SPI") (pin "P$6") (pinfunction "6_P$6") (pintype "bidirectional"))
      (node (ref "STEERING-MOTOR-ENCODER") (pin "P$2") (pinfunction "2_P$2") (pintype "passive"))
      (node (ref "TDN3-1211WI") (pin "VIN-") (pinfunction "VIN-_VIN-") (pintype "bidirectional"))
      (node (ref "TDN3-1211WI") (pin "VOUT-") (pinfunction "VOUT-_VOUT-") (pintype "bidirectional"))
      (node (ref "TEENSY3.6") (pin "AGND") (pinfunction "AGND_AGND") (pintype "power_in"))
      (node (ref "TEENSY3.6") (pin "GND") (pinfunction "GND_GND") (pintype "power_in"))
      (node (ref "TEENSY3.6") (pin "GND1") (pinfunction "GND_GND1") (pintype "power_in"))
      (node (ref "UART") (pin "4") (pinfunction "S_4") (pintype "passive"))
      (node (ref "Z-A1") (pin "A") (pinfunction "A_A") (pintype "passive"))
      (node (ref "Z-A2") (pin "A") (pinfunction "A_A") (pintype "passive"))
      (node (ref "Z-A3") (pin "A") (pinfunction "A_A") (pintype "passive"))
      (node (ref "Z-A6") (pin "A") (pinfunction "A_A") (pintype "passive"))
      (node (ref "Z-A7") (pin "A") (pinfunction "A_A") (pintype "passive"))
      (node (ref "Z-A8") (pin "A") (pinfunction "A_A") (pintype "passive"))
      (node (ref "Z-A9") (pin "A") (pinfunction "A_A") (pintype "passive"))
      (node (ref "Z-BV") (pin "A") (pinfunction "A_A") (pintype "passive"))
      (node (ref "Z-S1") (pin "A") (pinfunction "A_A") (pintype "passive"))
      (node (ref "Z-S2") (pin "A") (pinfunction "A_A") (pintype "passive"))
      (node (ref "Z-S3") (pin "A") (pinfunction "A_A") (pintype "passive"))
    )
    (net (code "22") (name "MISO-3V3") (class "Default")
      (node (ref "SPI") (pin "P$1") (pinfunction "1_P$1") (pintype "bidirectional"))
      (node (ref "TEENSY3.6") (pin "12") (pinfunction "12/MISO0_12") (pintype "bidirectional"))
      (node (ref "Z-S2") (pin "C") (pinfunction "C_C") (pintype "passive"))
    )
    (net (code "23") (name "MOSI-3V3") (class "Default")
      (node (ref "SPI") (pin "P$4") (pinfunction "4_P$4") (pintype "bidirectional"))
      (node (ref "TEENSY3.6") (pin "11") (pinfunction "11/MOSI0_11") (pintype "bidirectional"))
      (node (ref "Z-S3") (pin "C") (pinfunction "C_C") (pintype "passive"))
    )
    (net (code "24") (name "Net-(BRAKE-MOTOR-ENCODER-1)") (class "Default")
      (node (ref "BRAKE-MOTOR-ENCODER") (pin "P$1") (pinfunction "1_P$1") (pintype "passive"))
      (node (ref "R-A8M") (pin "2") (pinfunction "2_2") (pintype "passive"))
      (node (ref "R-A8U") (pin "1") (pinfunction "1_1") (pintype "passive"))
    )
    (net (code "25") (name "Net-(BRAKE-MOTOR-ENCODER-4)") (class "Default")
      (node (ref "BRAKE-MOTOR-ENCODER") (pin "P$4") (pinfunction "4_P$4") (pintype "passive"))
      (node (ref "R-A9M") (pin "2") (pinfunction "2_2") (pintype "passive"))
      (node (ref "R-A9U") (pin "1") (pinfunction "1_1") (pintype "passive"))
    )
    (net (code "26") (name "Net-(BUZZER-Pad4)") (class "Default")
      (node (ref "BUZZER") (pin "4") (pinfunction "4_4") (pintype "passive"))
      (node (ref "R-BZ") (pin "2") (pinfunction "2_2") (pintype "passive"))
    )
    (net (code "27") (name "Net-(C-CANH-Pad2)") (class "Default")
      (node (ref "C-CANH") (pin "2") (pinfunction "2_2") (pintype "passive"))
      (node (ref "R-CANH") (pin "1") (pinfunction "1_1") (pintype "passive"))
    )
    (net (code "28") (name "Net-(C-CANL-Pad2)") (class "Default")
      (node (ref "C-CANL") (pin "2") (pinfunction "2_2") (pintype "passive"))
      (node (ref "R-CANL") (pin "1") (pinfunction "1_1") (pintype "passive"))
    )
    (net (code "29") (name "Net-(LED-F-PadA)") (class "Default")
      (node (ref "LED-F") (pin "A") (pinfunction "A_A") (pintype "passive"))
      (node (ref "R-LF") (pin "1") (pinfunction "1_1") (pintype "passive"))
    )
    (net (code "30") (name "Net-(LED1-PadA)") (class "Default")
      (node (ref "LED1") (pin "A") (pinfunction "A_A") (pintype "passive"))
      (node (ref "R-L1") (pin "1") (pinfunction "1_1") (pintype "passive"))
    )
    (net (code "31") (name "Net-(LED2-PadA)") (class "Default")
      (node (ref "LED2") (pin "A") (pinfunction "A_A") (pintype "passive"))
      (node (ref "R-L2") (pin "1") (pinfunction "1_1") (pintype "passive"))
    )
    (net (code "32") (name "Net-(LIN-1)") (class "Default")
      (node (ref "C-12V1") (pin "+") (pinfunction "+_+") (pintype "passive"))
      (node (ref "DIN") (pin "C") (pinfunction "C_C") (pintype "passive"))
      (node (ref "LIN") (pin "P$1") (pinfunction "1_P$1") (pintype "passive"))
    )
    (net (code "33") (name "Net-(MCP2551-RS)") (class "Default")
      (node (ref "MCP2551") (pin "8") (pinfunction "RS_8") (pintype "bidirectional"))
      (node (ref "R-TCD") (pin "2") (pinfunction "2_2") (pintype "passive"))
    )
    (net (code "34") (name "Net-(PWM-ADC3-4)") (class "Default")
      (node (ref "PWM-ADC3") (pin "P$4") (pinfunction "4_P$4") (pintype "passive"))
      (node (ref "Q-T4") (pin "3") (pinfunction "D_3") (pintype "passive"))
      (node (ref "R-T4H") (pin "1") (pinfunction "1_1") (pintype "passive"))
    )
    (net (code "35") (name "Net-(Q-BZ-D)") (class "Default")
      (node (ref "Q-BZ") (pin "3") (pinfunction "D_3") (pintype "passive"))
      (node (ref "R-BZ") (pin "1") (pinfunction "1_1") (pintype "passive"))
    )
    (net (code "36") (name "Net-(R-A6M-Pad2)") (class "Default")
      (node (ref "R-A6M") (pin "2") (pinfunction "2_2") (pintype "passive"))
      (node (ref "X-ADC") (pin "1") (pinfunction "1_1") (pintype "passive"))
    )
    (net (code "37") (name "Net-(R-A7M-Pad2)") (class "Default")
      (node (ref "R-A7M") (pin "2") (pinfunction "2_2") (pintype "passive"))
      (node (ref "X-ADC") (pin "2") (pinfunction "2_2") (pintype "passive"))
    )
    (net (code "38") (name "Net-(STEERING-MOTOR-ENCODER-1)") (class "Default")
      (node (ref "R-A1M") (pin "2") (pinfunction "2_2") (pintype "passive"))
      (node (ref "R-A1U") (pin "1") (pinfunction "1_1") (pintype "passive"))
      (node (ref "STEERING-MOTOR-ENCODER") (pin "P$1") (pinfunction "1_P$1") (pintype "passive"))
    )
    (net (code "39") (name "Net-(STEERING-MOTOR-ENCODER-4)") (class "Default")
      (node (ref "R-A2M") (pin "2") (pinfunction "2_2") (pintype "passive"))
      (node (ref "R-A2U") (pin "1") (pinfunction "1_1") (pintype "passive"))
      (node (ref "STEERING-MOTOR-ENCODER") (pin "P$4") (pinfunction "4_P$4") (pintype "passive"))
    )
    (net (code "40") (name "Net-(TEENSY3.6-A21{slash}DAC0)") (class "Default")
      (node (ref "DAC") (pin "1") (pinfunction "1_1") (pintype "passive"))
      (node (ref "TEENSY3.6") (pin "A21") (pinfunction "A21/DAC0_A21") (pintype "bidirectional"))
    )
    (net (code "41") (name "PWM-3V3") (class "Default")
      (node (ref "Q-T4") (pin "2") (pinfunction "S_2") (pintype "passive"))
      (node (ref "R-T4L") (pin "1") (pinfunction "1_1") (pintype "passive"))
      (node (ref "TEENSY3.6") (pin "36/A17") (pinfunction "36/A17/PWM_36/A17") (pintype "bidirectional"))
    )
    (net (code "42") (name "S-ENC-A") (class "Default")
      (node (ref "C-A2") (pin "1") (pinfunction "1_1") (pintype "passive"))
      (node (ref "R-A2D") (pin "2") (pinfunction "2_2") (pintype "passive"))
      (node (ref "R-A2M") (pin "1") (pinfunction "1_1") (pintype "passive"))
      (node (ref "TEENSY3.6") (pin "29") (pinfunction "29/T/PWM_29") (pintype "bidirectional"))
      (node (ref "Z-A2") (pin "C") (pinfunction "C_C") (pintype "passive"))
    )
    (net (code "43") (name "S-ENC-B") (class "Default")
      (node (ref "C-A1") (pin "1") (pinfunction "1_1") (pintype "passive"))
      (node (ref "R-A1D") (pin "2") (pinfunction "2_2") (pintype "passive"))
      (node (ref "R-A1M") (pin "1") (pinfunction "1_1") (pintype "passive"))
      (node (ref "TEENSY3.6") (pin "30") (pinfunction "30/T/PWM_30") (pintype "bidirectional"))
      (node (ref "Z-A1") (pin "C") (pinfunction "C_C") (pintype "passive"))
    )
    (net (code "44") (name "SCK-3V3") (class "Default")
      (node (ref "SPI") (pin "P$3") (pinfunction "3_P$3") (pintype "bidirectional"))
      (node (ref "TEENSY3.6") (pin "13") (pinfunction "13/SCK0/LED_13") (pintype "bidirectional"))
      (node (ref "Z-S1") (pin "C") (pinfunction "C_C") (pintype "passive"))
    )
    (net (code "45") (name "SCL-3V3") (class "Default")
      (node (ref "9250") (pin "P$SCL") (pinfunction "SCL_P$SCL") (pintype "bidirectional"))
      (node (ref "I2C") (pin "2") (pinfunction "S_2") (pintype "passive"))
      (node (ref "I2C1") (pin "2") (pinfunction "S_2") (pintype "passive"))
      (node (ref "LIDAR-1") (pin "P$4") (pinfunction "4_P$4") (pintype "passive"))
      (node (ref "R-PU2") (pin "1") (pinfunction "1_1") (pintype "passive"))
      (node (ref "TEENSY3.6") (pin "19/A5") (pinfunction "19/A5/T/SCL0_19/A5") (pintype "bidirectional"))
    )
    (net (code "46") (name "SCL1-3V3") (class "Default")
      (node (ref "LIDAR-2") (pin "P$4") (pinfunction "4_P$4") (pintype "passive"))
      (node (ref "R-PU4") (pin "1") (pinfunction "1_1") (pintype "passive"))
      (node (ref "SONAR") (pin "P$4") (pinfunction "4_P$4") (pintype "passive"))
      (node (ref "TEENSY3.6") (pin "37/A18") (pinfunction "37/A18/SCL1/PWM_37/A18") (pintype "bidirectional"))
    )
    (net (code "47") (name "SDA-3V3") (class "Default")
      (node (ref "9250") (pin "P$SDA") (pinfunction "SDA_P$SDA") (pintype "bidirectional"))
      (node (ref "I2C") (pin "1") (pinfunction "S_1") (pintype "passive"))
      (node (ref "I2C1") (pin "1") (pinfunction "S_1") (pintype "passive"))
      (node (ref "LIDAR-1") (pin "P$1") (pinfunction "1_P$1") (pintype "passive"))
      (node (ref "R-PU1") (pin "1") (pinfunction "1_1") (pintype "passive"))
      (node (ref "TEENSY3.6") (pin "18/A4") (pinfunction "18/A4/T/SDA0_18/A4") (pintype "bidirectional"))
    )
    (net (code "48") (name "SDA1-3V3") (class "Default")
      (node (ref "LIDAR-2") (pin "P$1") (pinfunction "1_P$1") (pintype "passive"))
      (node (ref "R-PU3") (pin "1") (pinfunction "1_1") (pintype "passive"))
      (node (ref "SONAR") (pin "P$1") (pinfunction "1_P$1") (pintype "passive"))
      (node (ref "TEENSY3.6") (pin "38/A19") (pinfunction "38/A19/SDA1/PWM_38/A19") (pintype "bidirectional"))
    )
    (net (code "49") (name "TESTLED") (class "Default")
      (node (ref "R-L1") (pin "2") (pinfunction "2_2") (pintype "passive"))
      (node (ref "TEENSY3.6") (pin "33/A14") (pinfunction "33/A14/TX5/CAN1-TX_33/A14") (pintype "bidirectional"))
    )
    (net (code "50") (name "TESTLED2") (class "Default")
      (node (ref "R-L2") (pin "2") (pinfunction "2_2") (pintype "passive"))
      (node (ref "TEENSY3.6") (pin "39/A20") (pinfunction "39/A20_39/A20") (pintype "bidirectional"))
    )
    (net (code "51") (name "VBAT") (class "Default")
      (node (ref "DIN") (pin "A") (pinfunction "A_A") (pintype "passive"))
      (node (ref "MAIN_FUSE") (pin "PIN1") (pinfunction "PIN1_PIN1") (pintype "bidirectional"))
      (node (ref "R-BV1") (pin "2") (pinfunction "2_2") (pintype "passive"))
    )
    (net (code "52") (name "VDD") (class "Default")
      (node (ref "MAIN_FUSE") (pin "PIN2") (pinfunction "PIN2_PIN2") (pintype "bidirectional"))
      (node (ref "P_D") (pin "P$3") (pinfunction "3_P$3") (pintype "passive"))
    )
    (net (code "53") (name "unconnected-(9250-ADO-PadP$ADO)") (class "Default")
      (node (ref "9250") (pin "P$ADO") (pinfunction "ADO_P$ADO") (pintype "bidirectional"))
    )
    (net (code "54") (name "unconnected-(9250-ECL-PadP$ECL)") (class "Default")
      (node (ref "9250") (pin "P$ECL") (pinfunction "ECL_P$ECL") (pintype "bidirectional"))
    )
    (net (code "55") (name "unconnected-(9250-EDA-PadP$EDA)") (class "Default")
      (node (ref "9250") (pin "P$EDA") (pinfunction "EDA_P$EDA") (pintype "bidirectional"))
    )
    (net (code "56") (name "unconnected-(9250-FSYNC-PadP$FSYNC)") (class "Default")
      (node (ref "9250") (pin "P$FSYNC") (pinfunction "FSYNC_P$FSYNC") (pintype "bidirectional"))
    )
    (net (code "57") (name "unconnected-(9250-INT-PadP$INT)") (class "Default")
      (node (ref "9250") (pin "P$INT") (pinfunction "INT_P$INT") (pintype "bidirectional"))
    )
    (net (code "58") (name "unconnected-(9250-NCS-PadP$NCS)") (class "Default")
      (node (ref "9250") (pin "P$NCS") (pinfunction "NCS_P$NCS") (pintype "bidirectional"))
    )
    (net (code "59") (name "unconnected-(BUZZER-Pad2)") (class "Default")
      (node (ref "BUZZER") (pin "2") (pinfunction "2_2") (pintype "passive"))
    )
    (net (code "60") (name "unconnected-(BUZZER-Pad3)") (class "Default")
      (node (ref "BUZZER") (pin "3") (pinfunction "3_3") (pintype "passive"))
    )
    (net (code "61") (name "unconnected-(MCP2551-VREF-Pad5)") (class "Default")
      (node (ref "MCP2551") (pin "5") (pinfunction "VREF_5") (pintype "bidirectional"))
    )
    (net (code "62") (name "unconnected-(SPI-5-PadP$5)") (class "Default")
      (node (ref "SPI") (pin "P$5") (pinfunction "5_P$5") (pintype "bidirectional"))
    )
    (net (code "63") (name "unconnected-(TDN3-1211WI-ON{slash}OFF-PadONOFF)") (class "Default")
      (node (ref "TDN3-1211WI") (pin "ONOFF") (pinfunction "ON/OFF_ONOFF") (pintype "bidirectional"))
    )
    (net (code "64") (name "unconnected-(TEENSY3.6-2{slash}PWM-Pad2)") (class "Default")
      (node (ref "TEENSY3.6") (pin "2") (pinfunction "2/PWM_2") (pintype "bidirectional"))
    )
    (net (code "65") (name "unconnected-(TEENSY3.6-5{slash}PWM-Pad5)") (class "Default")
      (node (ref "TEENSY3.6") (pin "5") (pinfunction "5/PWM_5") (pintype "bidirectional"))
    )
    (net (code "66") (name "unconnected-(TEENSY3.6-6{slash}PWM-Pad6)") (class "Default")
      (node (ref "TEENSY3.6") (pin "6") (pinfunction "6/PWM_6") (pintype "bidirectional"))
    )
    (net (code "67") (name "unconnected-(TEENSY3.6-7{slash}RX3{slash}PWM-Pad7)") (class "Default")
      (node (ref "TEENSY3.6") (pin "7") (pinfunction "7/RX3/PWM_7") (pintype "bidirectional"))
    )
    (net (code "68") (name "unconnected-(TEENSY3.6-8{slash}TX3{slash}PWM-Pad8)") (class "Default")
      (node (ref "TEENSY3.6") (pin "8") (pinfunction "8/TX3/PWM_8") (pintype "bidirectional"))
    )
    (net (code "69") (name "unconnected-(TEENSY3.6-9{slash}RX2{slash}PWM-Pad9)") (class "Default")
      (node (ref "TEENSY3.6") (pin "9") (pinfunction "9/RX2/PWM_9") (pintype "bidirectional"))
    )
    (net (code "70") (name "unconnected-(TEENSY3.6-10{slash}TX2{slash}PWM-Pad10)") (class "Default")
      (node (ref "TEENSY3.6") (pin "10") (pinfunction "10/TX2/PWM_10") (pintype "bidirectional"))
    )
    (net (code "71") (name "unconnected-(TEENSY3.6-14{slash}A0{slash}PWM-Pad14{slash}A0)") (class "Default")
      (node (ref "TEENSY3.6") (pin "14/A0") (pinfunction "14/A0/PWM_14/A0") (pintype "bidirectional"))
    )
    (net (code "72") (name "unconnected-(TEENSY3.6-15{slash}A1{slash}T-Pad15{slash}A1)") (class "Default")
      (node (ref "TEENSY3.6") (pin "15/A1") (pinfunction "15/A1/T_15/A1") (pintype "bidirectional"))
    )
    (net (code "73") (name "unconnected-(TEENSY3.6-16{slash}A2{slash}T{slash}PWM-Pad16{slash}A2)") (class "Default")
      (node (ref "TEENSY3.6") (pin "16/A2") (pinfunction "16/A2/T/PWM_16/A2") (pintype "bidirectional"))
    )
    (net (code "74") (name "unconnected-(TEENSY3.6-22{slash}A8{slash}T{slash}PWM-Pad22{slash}A8)") (class "Default")
      (node (ref "TEENSY3.6") (pin "22/A8") (pinfunction "22/A8/T/PWM_22/A8") (pintype "bidirectional"))
    )
    (net (code "75") (name "unconnected-(TEENSY3.6-23{slash}A9{slash}T{slash}PWM-Pad23{slash}A9)") (class "Default")
      (node (ref "TEENSY3.6") (pin "23/A9") (pinfunction "23/A9/T/PWM_23/A9") (pintype "bidirectional"))
    )
    (net (code "76") (name "unconnected-(TEENSY3.6-A22{slash}DAC1-PadA22)") (class "Default")
      (node (ref "TEENSY3.6") (pin "A22") (pinfunction "A22/DAC1_A22") (pintype "bidirectional"))
    )
    (net (code "77") (name "unconnected-(TEENSY3.6-Pad24)") (class "Default")
      (node (ref "TEENSY3.6") (pin "24") (pinfunction "24_24") (pintype "bidirectional"))
    )
    (net (code "78") (name "unconnected-(TEENSY3.6-Pad25)") (class "Default")
      (node (ref "TEENSY3.6") (pin "25") (pinfunction "25_25") (pintype "bidirectional"))
    )
    (net (code "79") (name "unconnected-(TEENSY3.6-Pad26)") (class "Default")
      (node (ref "TEENSY3.6") (pin "26") (pinfunction "26_26") (pintype "bidirectional"))
    )
    (net (code "80") (name "unconnected-(TEENSY3.6-Pad27)") (class "Default")
      (node (ref "TEENSY3.6") (pin "27") (pinfunction "27_27") (pintype "bidirectional"))
    )
    (net (code "81") (name "unconnected-(TEENSY3.6-Pad28)") (class "Default")
      (node (ref "TEENSY3.6") (pin "28") (pinfunction "28_28") (pintype "bidirectional"))
    )
  )
)
